# Fsociety_Keyboard_SCH_Cherry.net
KiCad netlist of a schematic drawn in Altium Designer
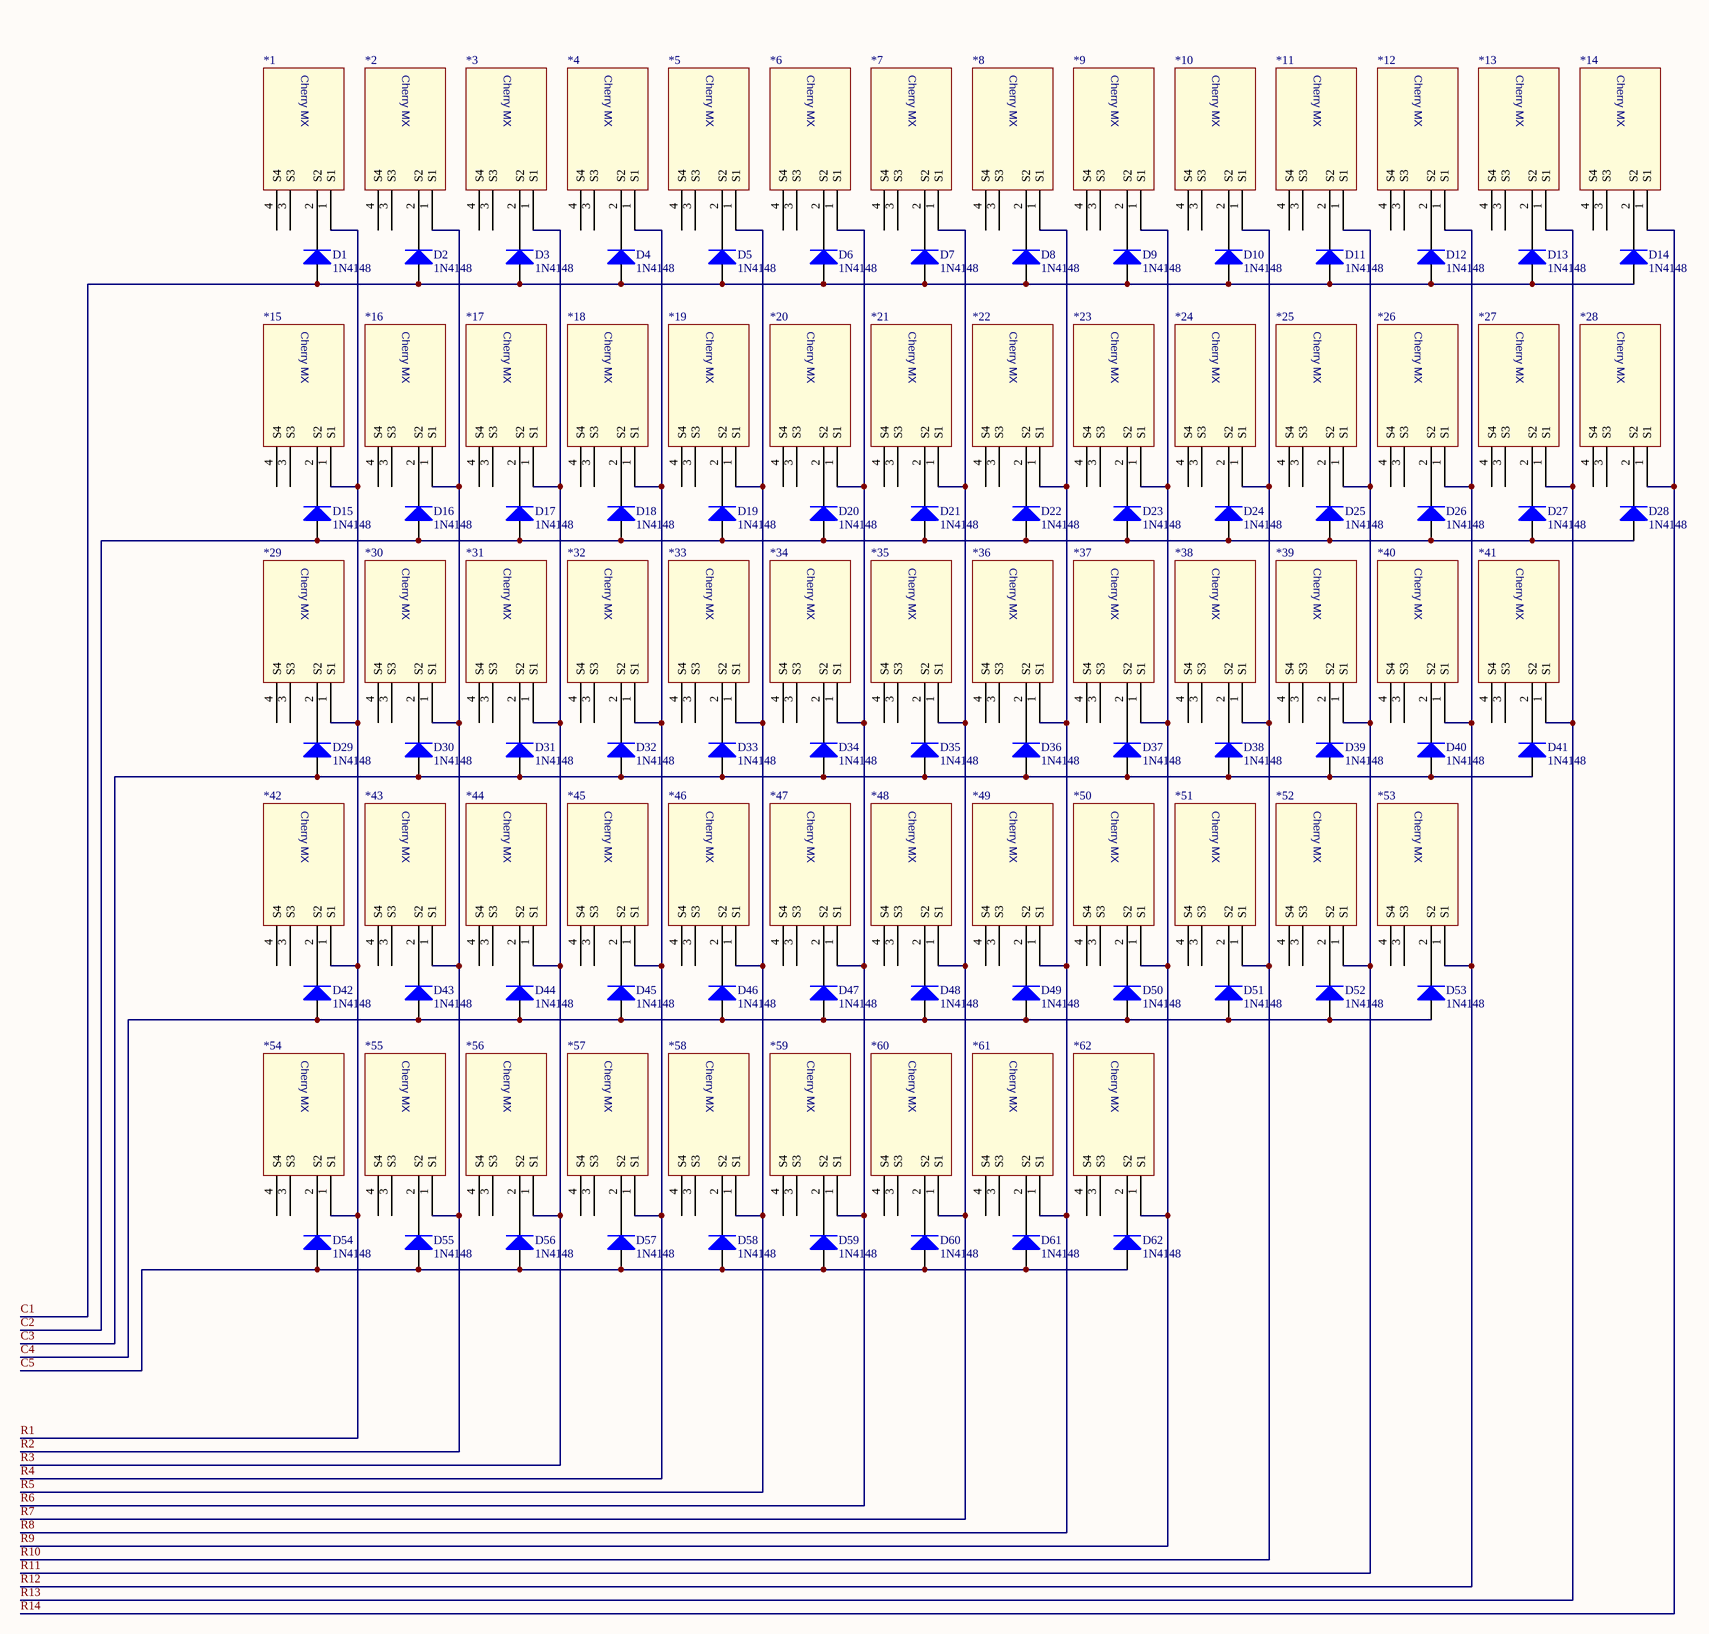
[diagram p0: Fsociety_Keyboard_SCH_Cherry.SchDoc]

(export (version "E")
  (design (tool "Eeschema 10.0.6"))
  (components
    (comp (ref "*1")
      (value "CHERRY_MX")
      (footprint "CherryMX")
      (libsource (lib "Sumasta_new") (part "CHERRY_MX"))
    )
    (comp (ref "*2")
      (value "CHERRY_MX")
      (footprint "CherryMX")
      (libsource (lib "Sumasta_new") (part "CHERRY_MX"))
    )
    (comp (ref "*3")
      (value "CHERRY_MX")
      (footprint "CherryMX")
      (libsource (lib "Sumasta_new") (part "CHERRY_MX"))
    )
    (comp (ref "*4")
      (value "CHERRY_MX")
      (footprint "CherryMX")
      (libsource (lib "Sumasta_new") (part "CHERRY_MX"))
    )
    (comp (ref "*5")
      (value "CHERRY_MX")
      (footprint "CherryMX")
      (libsource (lib "Sumasta_new") (part "CHERRY_MX"))
    )
    (comp (ref "*6")
      (value "CHERRY_MX")
      (footprint "CherryMX")
      (libsource (lib "Sumasta_new") (part "CHERRY_MX"))
    )
    (comp (ref "*7")
      (value "CHERRY_MX")
      (footprint "CherryMX")
      (libsource (lib "Sumasta_new") (part "CHERRY_MX"))
    )
    (comp (ref "*8")
      (value "CHERRY_MX")
      (footprint "CherryMX")
      (libsource (lib "Sumasta_new") (part "CHERRY_MX"))
    )
    (comp (ref "*9")
      (value "CHERRY_MX")
      (footprint "CherryMX")
      (libsource (lib "Sumasta_new") (part "CHERRY_MX"))
    )
    (comp (ref "*10")
      (value "CHERRY_MX")
      (footprint "CherryMX")
      (libsource (lib "Sumasta_new") (part "CHERRY_MX"))
    )
    (comp (ref "*11")
      (value "CHERRY_MX")
      (footprint "CherryMX")
      (libsource (lib "Sumasta_new") (part "CHERRY_MX"))
    )
    (comp (ref "*12")
      (value "CHERRY_MX")
      (footprint "CherryMX")
      (libsource (lib "Sumasta_new") (part "CHERRY_MX"))
    )
    (comp (ref "*13")
      (value "CHERRY_MX")
      (footprint "CherryMX")
      (libsource (lib "Sumasta_new") (part "CHERRY_MX"))
    )
    (comp (ref "*14")
      (value "CHERRY_MX")
      (footprint "CherryMX")
      (libsource (lib "Sumasta_new") (part "CHERRY_MX"))
    )
    (comp (ref "*15")
      (value "CHERRY_MX")
      (footprint "CherryMX")
      (libsource (lib "Sumasta_new") (part "CHERRY_MX"))
    )
    (comp (ref "*16")
      (value "CHERRY_MX")
      (footprint "CherryMX")
      (libsource (lib "Sumasta_new") (part "CHERRY_MX"))
    )
    (comp (ref "*17")
      (value "CHERRY_MX")
      (footprint "CherryMX")
      (libsource (lib "Sumasta_new") (part "CHERRY_MX"))
    )
    (comp (ref "*18")
      (value "CHERRY_MX")
      (footprint "CherryMX")
      (libsource (lib "Sumasta_new") (part "CHERRY_MX"))
    )
    (comp (ref "*19")
      (value "CHERRY_MX")
      (footprint "CherryMX")
      (libsource (lib "Sumasta_new") (part "CHERRY_MX"))
    )
    (comp (ref "*20")
      (value "CHERRY_MX")
      (footprint "CherryMX")
      (libsource (lib "Sumasta_new") (part "CHERRY_MX"))
    )
    (comp (ref "*21")
      (value "CHERRY_MX")
      (footprint "CherryMX")
      (libsource (lib "Sumasta_new") (part "CHERRY_MX"))
    )
    (comp (ref "*22")
      (value "CHERRY_MX")
      (footprint "CherryMX")
      (libsource (lib "Sumasta_new") (part "CHERRY_MX"))
    )
    (comp (ref "*23")
      (value "CHERRY_MX")
      (footprint "CherryMX")
      (libsource (lib "Sumasta_new") (part "CHERRY_MX"))
    )
    (comp (ref "*24")
      (value "CHERRY_MX")
      (footprint "CherryMX")
      (libsource (lib "Sumasta_new") (part "CHERRY_MX"))
    )
    (comp (ref "*25")
      (value "CHERRY_MX")
      (footprint "CherryMX")
      (libsource (lib "Sumasta_new") (part "CHERRY_MX"))
    )
    (comp (ref "*26")
      (value "CHERRY_MX")
      (footprint "CherryMX")
      (libsource (lib "Sumasta_new") (part "CHERRY_MX"))
    )
    (comp (ref "*27")
      (value "CHERRY_MX")
      (footprint "CherryMX")
      (libsource (lib "Sumasta_new") (part "CHERRY_MX"))
    )
    (comp (ref "*28")
      (value "CHERRY_MX")
      (footprint "CherryMX")
      (libsource (lib "Sumasta_new") (part "CHERRY_MX"))
    )
    (comp (ref "*29")
      (value "CHERRY_MX")
      (footprint "CherryMX")
      (libsource (lib "Sumasta_new") (part "CHERRY_MX"))
    )
    (comp (ref "*30")
      (value "CHERRY_MX")
      (footprint "CherryMX")
      (libsource (lib "Sumasta_new") (part "CHERRY_MX"))
    )
    (comp (ref "*31")
      (value "CHERRY_MX")
      (footprint "CherryMX")
      (libsource (lib "Sumasta_new") (part "CHERRY_MX"))
    )
    (comp (ref "*32")
      (value "CHERRY_MX")
      (footprint "CherryMX")
      (libsource (lib "Sumasta_new") (part "CHERRY_MX"))
    )
    (comp (ref "*33")
      (value "CHERRY_MX")
      (footprint "CherryMX")
      (libsource (lib "Sumasta_new") (part "CHERRY_MX"))
    )
    (comp (ref "*34")
      (value "CHERRY_MX")
      (footprint "CherryMX")
      (libsource (lib "Sumasta_new") (part "CHERRY_MX"))
    )
    (comp (ref "*35")
      (value "CHERRY_MX")
      (footprint "CherryMX")
      (libsource (lib "Sumasta_new") (part "CHERRY_MX"))
    )
    (comp (ref "*36")
      (value "CHERRY_MX")
      (footprint "CherryMX")
      (libsource (lib "Sumasta_new") (part "CHERRY_MX"))
    )
    (comp (ref "*37")
      (value "CHERRY_MX")
      (footprint "CherryMX")
      (libsource (lib "Sumasta_new") (part "CHERRY_MX"))
    )
    (comp (ref "*38")
      (value "CHERRY_MX")
      (footprint "CherryMX")
      (libsource (lib "Sumasta_new") (part "CHERRY_MX"))
    )
    (comp (ref "*39")
      (value "CHERRY_MX")
      (footprint "CherryMX")
      (libsource (lib "Sumasta_new") (part "CHERRY_MX"))
    )
    (comp (ref "*40")
      (value "CHERRY_MX")
      (footprint "CherryMX")
      (libsource (lib "Sumasta_new") (part "CHERRY_MX"))
    )
    (comp (ref "*41")
      (value "CHERRY_MX")
      (footprint "CherryMX")
      (libsource (lib "Sumasta_new") (part "CHERRY_MX"))
    )
    (comp (ref "*42")
      (value "CHERRY_MX")
      (footprint "CherryMX")
      (libsource (lib "Sumasta_new") (part "CHERRY_MX"))
    )
    (comp (ref "*43")
      (value "CHERRY_MX")
      (footprint "CherryMX")
      (libsource (lib "Sumasta_new") (part "CHERRY_MX"))
    )
    (comp (ref "*44")
      (value "CHERRY_MX")
      (footprint "CherryMX")
      (libsource (lib "Sumasta_new") (part "CHERRY_MX"))
    )
    (comp (ref "*45")
      (value "CHERRY_MX")
      (footprint "CherryMX")
      (libsource (lib "Sumasta_new") (part "CHERRY_MX"))
    )
    (comp (ref "*46")
      (value "CHERRY_MX")
      (footprint "CherryMX")
      (libsource (lib "Sumasta_new") (part "CHERRY_MX"))
    )
    (comp (ref "*47")
      (value "CHERRY_MX")
      (footprint "CherryMX")
      (libsource (lib "Sumasta_new") (part "CHERRY_MX"))
    )
    (comp (ref "*48")
      (value "CHERRY_MX")
      (footprint "CherryMX")
      (libsource (lib "Sumasta_new") (part "CHERRY_MX"))
    )
    (comp (ref "*49")
      (value "CHERRY_MX")
      (footprint "CherryMX")
      (libsource (lib "Sumasta_new") (part "CHERRY_MX"))
    )
    (comp (ref "*50")
      (value "CHERRY_MX")
      (footprint "CherryMX")
      (libsource (lib "Sumasta_new") (part "CHERRY_MX"))
    )
    (comp (ref "*51")
      (value "CHERRY_MX")
      (footprint "CherryMX")
      (libsource (lib "Sumasta_new") (part "CHERRY_MX"))
    )
    (comp (ref "*52")
      (value "CHERRY_MX")
      (footprint "CherryMX")
      (libsource (lib "Sumasta_new") (part "CHERRY_MX"))
    )
    (comp (ref "*53")
      (value "CHERRY_MX")
      (footprint "CherryMX")
      (libsource (lib "Sumasta_new") (part "CHERRY_MX"))
    )
    (comp (ref "*54")
      (value "CHERRY_MX")
      (footprint "CherryMX")
      (libsource (lib "Sumasta_new") (part "CHERRY_MX"))
    )
    (comp (ref "*55")
      (value "CHERRY_MX")
      (footprint "CherryMX")
      (libsource (lib "Sumasta_new") (part "CHERRY_MX"))
    )
    (comp (ref "*56")
      (value "CHERRY_MX")
      (footprint "CherryMX")
      (libsource (lib "Sumasta_new") (part "CHERRY_MX"))
    )
    (comp (ref "*57")
      (value "CHERRY_MX")
      (footprint "CherryMX")
      (libsource (lib "Sumasta_new") (part "CHERRY_MX"))
    )
    (comp (ref "*58")
      (value "CHERRY_MX")
      (footprint "CherryMX")
      (libsource (lib "Sumasta_new") (part "CHERRY_MX"))
    )
    (comp (ref "*59")
      (value "CHERRY_MX")
      (footprint "CherryMX")
      (libsource (lib "Sumasta_new") (part "CHERRY_MX"))
    )
    (comp (ref "*60")
      (value "CHERRY_MX")
      (footprint "CherryMX")
      (libsource (lib "Sumasta_new") (part "CHERRY_MX"))
    )
    (comp (ref "*61")
      (value "CHERRY_MX")
      (footprint "CherryMX")
      (libsource (lib "Sumasta_new") (part "CHERRY_MX"))
    )
    (comp (ref "*62")
      (value "CHERRY_MX")
      (footprint "CherryMX")
      (libsource (lib "Sumasta_new") (part "CHERRY_MX"))
    )
    (comp (ref "D1")
      (value "1N4148")
      (footprint "DIOMELF3515_NR_SOD80C")
      (description "Diode 1N4148 SOD80(SMT)")
      (fields (field (name "MAXPARTNUMBER") "1N4148!") (field (name "PARTNUMBER") "LL4148-GS18-LF"))
      (libsource (lib "RENA Vault") (part "DIODE"))
    )
    (comp (ref "D2")
      (value "1N4148")
      (footprint "DIOMELF3515_NR_SOD80C")
      (description "Diode 1N4148 SOD80(SMT)")
      (fields (field (name "MAXPARTNUMBER") "1N4148!") (field (name "PARTNUMBER") "LL4148-GS18-LF"))
      (libsource (lib "RENA Vault") (part "DIODE"))
    )
    (comp (ref "D3")
      (value "1N4148")
      (footprint "DIOMELF3515_NR_SOD80C")
      (description "Diode 1N4148 SOD80(SMT)")
      (fields (field (name "MAXPARTNUMBER") "1N4148!") (field (name "PARTNUMBER") "LL4148-GS18-LF"))
      (libsource (lib "RENA Vault") (part "DIODE"))
    )
    (comp (ref "D4")
      (value "1N4148")
      (footprint "DIOMELF3515_NR_SOD80C")
      (description "Diode 1N4148 SOD80(SMT)")
      (fields (field (name "MAXPARTNUMBER") "1N4148!") (field (name "PARTNUMBER") "LL4148-GS18-LF"))
      (libsource (lib "RENA Vault") (part "DIODE"))
    )
    (comp (ref "D5")
      (value "1N4148")
      (footprint "DIOMELF3515_NR_SOD80C")
      (description "Diode 1N4148 SOD80(SMT)")
      (fields (field (name "MAXPARTNUMBER") "1N4148!") (field (name "PARTNUMBER") "LL4148-GS18-LF"))
      (libsource (lib "RENA Vault") (part "DIODE"))
    )
    (comp (ref "D6")
      (value "1N4148")
      (footprint "DIOMELF3515_NR_SOD80C")
      (description "Diode 1N4148 SOD80(SMT)")
      (fields (field (name "MAXPARTNUMBER") "1N4148!") (field (name "PARTNUMBER") "LL4148-GS18-LF"))
      (libsource (lib "RENA Vault") (part "DIODE"))
    )
    (comp (ref "D7")
      (value "1N4148")
      (footprint "DIOMELF3515_NR_SOD80C")
      (description "Diode 1N4148 SOD80(SMT)")
      (fields (field (name "MAXPARTNUMBER") "1N4148!") (field (name "PARTNUMBER") "LL4148-GS18-LF"))
      (libsource (lib "RENA Vault") (part "DIODE"))
    )
    (comp (ref "D8")
      (value "1N4148")
      (footprint "DIOMELF3515_NR_SOD80C")
      (description "Diode 1N4148 SOD80(SMT)")
      (fields (field (name "MAXPARTNUMBER") "1N4148!") (field (name "PARTNUMBER") "LL4148-GS18-LF"))
      (libsource (lib "RENA Vault") (part "DIODE"))
    )
    (comp (ref "D9")
      (value "1N4148")
      (footprint "DIOMELF3515_NR_SOD80C")
      (description "Diode 1N4148 SOD80(SMT)")
      (fields (field (name "MAXPARTNUMBER") "1N4148!") (field (name "PARTNUMBER") "LL4148-GS18-LF"))
      (libsource (lib "RENA Vault") (part "DIODE"))
    )
    (comp (ref "D10")
      (value "1N4148")
      (footprint "DIOMELF3515_NR_SOD80C")
      (description "Diode 1N4148 SOD80(SMT)")
      (fields (field (name "MAXPARTNUMBER") "1N4148!") (field (name "PARTNUMBER") "LL4148-GS18-LF"))
      (libsource (lib "RENA Vault") (part "DIODE"))
    )
    (comp (ref "D11")
      (value "1N4148")
      (footprint "DIOMELF3515_NR_SOD80C")
      (description "Diode 1N4148 SOD80(SMT)")
      (fields (field (name "MAXPARTNUMBER") "1N4148!") (field (name "PARTNUMBER") "LL4148-GS18-LF"))
      (libsource (lib "RENA Vault") (part "DIODE"))
    )
    (comp (ref "D12")
      (value "1N4148")
      (footprint "DIOMELF3515_NR_SOD80C")
      (description "Diode 1N4148 SOD80(SMT)")
      (fields (field (name "MAXPARTNUMBER") "1N4148!") (field (name "PARTNUMBER") "LL4148-GS18-LF"))
      (libsource (lib "RENA Vault") (part "DIODE"))
    )
    (comp (ref "D13")
      (value "1N4148")
      (footprint "DIOMELF3515_NR_SOD80C")
      (description "Diode 1N4148 SOD80(SMT)")
      (fields (field (name "MAXPARTNUMBER") "1N4148!") (field (name "PARTNUMBER") "LL4148-GS18-LF"))
      (libsource (lib "RENA Vault") (part "DIODE"))
    )
    (comp (ref "D14")
      (value "1N4148")
      (footprint "DIOMELF3515_NR_SOD80C")
      (description "Diode 1N4148 SOD80(SMT)")
      (fields (field (name "MAXPARTNUMBER") "1N4148!") (field (name "PARTNUMBER") "LL4148-GS18-LF"))
      (libsource (lib "RENA Vault") (part "DIODE"))
    )
    (comp (ref "D15")
      (value "1N4148")
      (footprint "DIOMELF3515_NR_SOD80C")
      (description "Diode 1N4148 SOD80(SMT)")
      (fields (field (name "MAXPARTNUMBER") "1N4148!") (field (name "PARTNUMBER") "LL4148-GS18-LF"))
      (libsource (lib "RENA Vault") (part "DIODE"))
    )
    (comp (ref "D16")
      (value "1N4148")
      (footprint "DIOMELF3515_NR_SOD80C")
      (description "Diode 1N4148 SOD80(SMT)")
      (fields (field (name "MAXPARTNUMBER") "1N4148!") (field (name "PARTNUMBER") "LL4148-GS18-LF"))
      (libsource (lib "RENA Vault") (part "DIODE"))
    )
    (comp (ref "D17")
      (value "1N4148")
      (footprint "DIOMELF3515_NR_SOD80C")
      (description "Diode 1N4148 SOD80(SMT)")
      (fields (field (name "MAXPARTNUMBER") "1N4148!") (field (name "PARTNUMBER") "LL4148-GS18-LF"))
      (libsource (lib "RENA Vault") (part "DIODE"))
    )
    (comp (ref "D18")
      (value "1N4148")
      (footprint "DIOMELF3515_NR_SOD80C")
      (description "Diode 1N4148 SOD80(SMT)")
      (fields (field (name "MAXPARTNUMBER") "1N4148!") (field (name "PARTNUMBER") "LL4148-GS18-LF"))
      (libsource (lib "RENA Vault") (part "DIODE"))
    )
    (comp (ref "D19")
      (value "1N4148")
      (footprint "DIOMELF3515_NR_SOD80C")
      (description "Diode 1N4148 SOD80(SMT)")
      (fields (field (name "MAXPARTNUMBER") "1N4148!") (field (name "PARTNUMBER") "LL4148-GS18-LF"))
      (libsource (lib "RENA Vault") (part "DIODE"))
    )
    (comp (ref "D20")
      (value "1N4148")
      (footprint "DIOMELF3515_NR_SOD80C")
      (description "Diode 1N4148 SOD80(SMT)")
      (fields (field (name "MAXPARTNUMBER") "1N4148!") (field (name "PARTNUMBER") "LL4148-GS18-LF"))
      (libsource (lib "RENA Vault") (part "DIODE"))
    )
    (comp (ref "D21")
      (value "1N4148")
      (footprint "DIOMELF3515_NR_SOD80C")
      (description "Diode 1N4148 SOD80(SMT)")
      (fields (field (name "MAXPARTNUMBER") "1N4148!") (field (name "PARTNUMBER") "LL4148-GS18-LF"))
      (libsource (lib "RENA Vault") (part "DIODE"))
    )
    (comp (ref "D22")
      (value "1N4148")
      (footprint "DIOMELF3515_NR_SOD80C")
      (description "Diode 1N4148 SOD80(SMT)")
      (fields (field (name "MAXPARTNUMBER") "1N4148!") (field (name "PARTNUMBER") "LL4148-GS18-LF"))
      (libsource (lib "RENA Vault") (part "DIODE"))
    )
    (comp (ref "D23")
      (value "1N4148")
      (footprint "DIOMELF3515_NR_SOD80C")
      (description "Diode 1N4148 SOD80(SMT)")
      (fields (field (name "MAXPARTNUMBER") "1N4148!") (field (name "PARTNUMBER") "LL4148-GS18-LF"))
      (libsource (lib "RENA Vault") (part "DIODE"))
    )
    (comp (ref "D24")
      (value "1N4148")
      (footprint "DIOMELF3515_NR_SOD80C")
      (description "Diode 1N4148 SOD80(SMT)")
      (fields (field (name "MAXPARTNUMBER") "1N4148!") (field (name "PARTNUMBER") "LL4148-GS18-LF"))
      (libsource (lib "RENA Vault") (part "DIODE"))
    )
    (comp (ref "D25")
      (value "1N4148")
      (footprint "DIOMELF3515_NR_SOD80C")
      (description "Diode 1N4148 SOD80(SMT)")
      (fields (field (name "MAXPARTNUMBER") "1N4148!") (field (name "PARTNUMBER") "LL4148-GS18-LF"))
      (libsource (lib "RENA Vault") (part "DIODE"))
    )
    (comp (ref "D26")
      (value "1N4148")
      (footprint "DIOMELF3515_NR_SOD80C")
      (description "Diode 1N4148 SOD80(SMT)")
      (fields (field (name "MAXPARTNUMBER") "1N4148!") (field (name "PARTNUMBER") "LL4148-GS18-LF"))
      (libsource (lib "RENA Vault") (part "DIODE"))
    )
    (comp (ref "D27")
      (value "1N4148")
      (footprint "DIOMELF3515_NR_SOD80C")
      (description "Diode 1N4148 SOD80(SMT)")
      (fields (field (name "MAXPARTNUMBER") "1N4148!") (field (name "PARTNUMBER") "LL4148-GS18-LF"))
      (libsource (lib "RENA Vault") (part "DIODE"))
    )
    (comp (ref "D28")
      (value "1N4148")
      (footprint "DIOMELF3515_NR_SOD80C")
      (description "Diode 1N4148 SOD80(SMT)")
      (fields (field (name "MAXPARTNUMBER") "1N4148!") (field (name "PARTNUMBER") "LL4148-GS18-LF"))
      (libsource (lib "RENA Vault") (part "DIODE"))
    )
    (comp (ref "D29")
      (value "1N4148")
      (footprint "DIOMELF3515_NR_SOD80C")
      (description "Diode 1N4148 SOD80(SMT)")
      (fields (field (name "MAXPARTNUMBER") "1N4148!") (field (name "PARTNUMBER") "LL4148-GS18-LF"))
      (libsource (lib "RENA Vault") (part "DIODE"))
    )
    (comp (ref "D30")
      (value "1N4148")
      (footprint "DIOMELF3515_NR_SOD80C")
      (description "Diode 1N4148 SOD80(SMT)")
      (fields (field (name "MAXPARTNUMBER") "1N4148!") (field (name "PARTNUMBER") "LL4148-GS18-LF"))
      (libsource (lib "RENA Vault") (part "DIODE"))
    )
    (comp (ref "D31")
      (value "1N4148")
      (footprint "DIOMELF3515_NR_SOD80C")
      (description "Diode 1N4148 SOD80(SMT)")
      (fields (field (name "MAXPARTNUMBER") "1N4148!") (field (name "PARTNUMBER") "LL4148-GS18-LF"))
      (libsource (lib "RENA Vault") (part "DIODE"))
    )
    (comp (ref "D32")
      (value "1N4148")
      (footprint "DIOMELF3515_NR_SOD80C")
      (description "Diode 1N4148 SOD80(SMT)")
      (fields (field (name "MAXPARTNUMBER") "1N4148!") (field (name "PARTNUMBER") "LL4148-GS18-LF"))
      (libsource (lib "RENA Vault") (part "DIODE"))
    )
    (comp (ref "D33")
      (value "1N4148")
      (footprint "DIOMELF3515_NR_SOD80C")
      (description "Diode 1N4148 SOD80(SMT)")
      (fields (field (name "MAXPARTNUMBER") "1N4148!") (field (name "PARTNUMBER") "LL4148-GS18-LF"))
      (libsource (lib "RENA Vault") (part "DIODE"))
    )
    (comp (ref "D34")
      (value "1N4148")
      (footprint "DIOMELF3515_NR_SOD80C")
      (description "Diode 1N4148 SOD80(SMT)")
      (fields (field (name "MAXPARTNUMBER") "1N4148!") (field (name "PARTNUMBER") "LL4148-GS18-LF"))
      (libsource (lib "RENA Vault") (part "DIODE"))
    )
    (comp (ref "D35")
      (value "1N4148")
      (footprint "DIOMELF3515_NR_SOD80C")
      (description "Diode 1N4148 SOD80(SMT)")
      (fields (field (name "MAXPARTNUMBER") "1N4148!") (field (name "PARTNUMBER") "LL4148-GS18-LF"))
      (libsource (lib "RENA Vault") (part "DIODE"))
    )
    (comp (ref "D36")
      (value "1N4148")
      (footprint "DIOMELF3515_NR_SOD80C")
      (description "Diode 1N4148 SOD80(SMT)")
      (fields (field (name "MAXPARTNUMBER") "1N4148!") (field (name "PARTNUMBER") "LL4148-GS18-LF"))
      (libsource (lib "RENA Vault") (part "DIODE"))
    )
    (comp (ref "D37")
      (value "1N4148")
      (footprint "DIOMELF3515_NR_SOD80C")
      (description "Diode 1N4148 SOD80(SMT)")
      (fields (field (name "MAXPARTNUMBER") "1N4148!") (field (name "PARTNUMBER") "LL4148-GS18-LF"))
      (libsource (lib "RENA Vault") (part "DIODE"))
    )
    (comp (ref "D38")
      (value "1N4148")
      (footprint "DIOMELF3515_NR_SOD80C")
      (description "Diode 1N4148 SOD80(SMT)")
      (fields (field (name "MAXPARTNUMBER") "1N4148!") (field (name "PARTNUMBER") "LL4148-GS18-LF"))
      (libsource (lib "RENA Vault") (part "DIODE"))
    )
    (comp (ref "D39")
      (value "1N4148")
      (footprint "DIOMELF3515_NR_SOD80C")
      (description "Diode 1N4148 SOD80(SMT)")
      (fields (field (name "MAXPARTNUMBER") "1N4148!") (field (name "PARTNUMBER") "LL4148-GS18-LF"))
      (libsource (lib "RENA Vault") (part "DIODE"))
    )
    (comp (ref "D40")
      (value "1N4148")
      (footprint "DIOMELF3515_NR_SOD80C")
      (description "Diode 1N4148 SOD80(SMT)")
      (fields (field (name "MAXPARTNUMBER") "1N4148!") (field (name "PARTNUMBER") "LL4148-GS18-LF"))
      (libsource (lib "RENA Vault") (part "DIODE"))
    )
    (comp (ref "D41")
      (value "1N4148")
      (footprint "DIOMELF3515_NR_SOD80C")
      (description "Diode 1N4148 SOD80(SMT)")
      (fields (field (name "MAXPARTNUMBER") "1N4148!") (field (name "PARTNUMBER") "LL4148-GS18-LF"))
      (libsource (lib "RENA Vault") (part "DIODE"))
    )
    (comp (ref "D42")
      (value "1N4148")
      (footprint "DIOMELF3515_NR_SOD80C")
      (description "Diode 1N4148 SOD80(SMT)")
      (fields (field (name "MAXPARTNUMBER") "1N4148!") (field (name "PARTNUMBER") "LL4148-GS18-LF"))
      (libsource (lib "RENA Vault") (part "DIODE"))
    )
    (comp (ref "D43")
      (value "1N4148")
      (footprint "DIOMELF3515_NR_SOD80C")
      (description "Diode 1N4148 SOD80(SMT)")
      (fields (field (name "MAXPARTNUMBER") "1N4148!") (field (name "PARTNUMBER") "LL4148-GS18-LF"))
      (libsource (lib "RENA Vault") (part "DIODE"))
    )
    (comp (ref "D44")
      (value "1N4148")
      (footprint "DIOMELF3515_NR_SOD80C")
      (description "Diode 1N4148 SOD80(SMT)")
      (fields (field (name "MAXPARTNUMBER") "1N4148!") (field (name "PARTNUMBER") "LL4148-GS18-LF"))
      (libsource (lib "RENA Vault") (part "DIODE"))
    )
    (comp (ref "D45")
      (value "1N4148")
      (footprint "DIOMELF3515_NR_SOD80C")
      (description "Diode 1N4148 SOD80(SMT)")
      (fields (field (name "MAXPARTNUMBER") "1N4148!") (field (name "PARTNUMBER") "LL4148-GS18-LF"))
      (libsource (lib "RENA Vault") (part "DIODE"))
    )
    (comp (ref "D46")
      (value "1N4148")
      (footprint "DIOMELF3515_NR_SOD80C")
      (description "Diode 1N4148 SOD80(SMT)")
      (fields (field (name "MAXPARTNUMBER") "1N4148!") (field (name "PARTNUMBER") "LL4148-GS18-LF"))
      (libsource (lib "RENA Vault") (part "DIODE"))
    )
    (comp (ref "D47")
      (value "1N4148")
      (footprint "DIOMELF3515_NR_SOD80C")
      (description "Diode 1N4148 SOD80(SMT)")
      (fields (field (name "MAXPARTNUMBER") "1N4148!") (field (name "PARTNUMBER") "LL4148-GS18-LF"))
      (libsource (lib "RENA Vault") (part "DIODE"))
    )
    (comp (ref "D48")
      (value "1N4148")
      (footprint "DIOMELF3515_NR_SOD80C")
      (description "Diode 1N4148 SOD80(SMT)")
      (fields (field (name "MAXPARTNUMBER") "1N4148!") (field (name "PARTNUMBER") "LL4148-GS18-LF"))
      (libsource (lib "RENA Vault") (part "DIODE"))
    )
    (comp (ref "D49")
      (value "1N4148")
      (footprint "DIOMELF3515_NR_SOD80C")
      (description "Diode 1N4148 SOD80(SMT)")
      (fields (field (name "MAXPARTNUMBER") "1N4148!") (field (name "PARTNUMBER") "LL4148-GS18-LF"))
      (libsource (lib "RENA Vault") (part "DIODE"))
    )
    (comp (ref "D50")
      (value "1N4148")
      (footprint "DIOMELF3515_NR_SOD80C")
      (description "Diode 1N4148 SOD80(SMT)")
      (fields (field (name "MAXPARTNUMBER") "1N4148!") (field (name "PARTNUMBER") "LL4148-GS18-LF"))
      (libsource (lib "RENA Vault") (part "DIODE"))
    )
    (comp (ref "D51")
      (value "1N4148")
      (footprint "DIOMELF3515_NR_SOD80C")
      (description "Diode 1N4148 SOD80(SMT)")
      (fields (field (name "MAXPARTNUMBER") "1N4148!") (field (name "PARTNUMBER") "LL4148-GS18-LF"))
      (libsource (lib "RENA Vault") (part "DIODE"))
    )
    (comp (ref "D52")
      (value "1N4148")
      (footprint "DIOMELF3515_NR_SOD80C")
      (description "Diode 1N4148 SOD80(SMT)")
      (fields (field (name "MAXPARTNUMBER") "1N4148!") (field (name "PARTNUMBER") "LL4148-GS18-LF"))
      (libsource (lib "RENA Vault") (part "DIODE"))
    )
    (comp (ref "D53")
      (value "1N4148")
      (footprint "DIOMELF3515_NR_SOD80C")
      (description "Diode 1N4148 SOD80(SMT)")
      (fields (field (name "MAXPARTNUMBER") "1N4148!") (field (name "PARTNUMBER") "LL4148-GS18-LF"))
      (libsource (lib "RENA Vault") (part "DIODE"))
    )
    (comp (ref "D54")
      (value "1N4148")
      (footprint "DIOMELF3515_NR_SOD80C")
      (description "Diode 1N4148 SOD80(SMT)")
      (fields (field (name "MAXPARTNUMBER") "1N4148!") (field (name "PARTNUMBER") "LL4148-GS18-LF"))
      (libsource (lib "RENA Vault") (part "DIODE"))
    )
    (comp (ref "D55")
      (value "1N4148")
      (footprint "DIOMELF3515_NR_SOD80C")
      (description "Diode 1N4148 SOD80(SMT)")
      (fields (field (name "MAXPARTNUMBER") "1N4148!") (field (name "PARTNUMBER") "LL4148-GS18-LF"))
      (libsource (lib "RENA Vault") (part "DIODE"))
    )
    (comp (ref "D56")
      (value "1N4148")
      (footprint "DIOMELF3515_NR_SOD80C")
      (description "Diode 1N4148 SOD80(SMT)")
      (fields (field (name "MAXPARTNUMBER") "1N4148!") (field (name "PARTNUMBER") "LL4148-GS18-LF"))
      (libsource (lib "RENA Vault") (part "DIODE"))
    )
    (comp (ref "D57")
      (value "1N4148")
      (footprint "DIOMELF3515_NR_SOD80C")
      (description "Diode 1N4148 SOD80(SMT)")
      (fields (field (name "MAXPARTNUMBER") "1N4148!") (field (name "PARTNUMBER") "LL4148-GS18-LF"))
      (libsource (lib "RENA Vault") (part "DIODE"))
    )
    (comp (ref "D58")
      (value "1N4148")
      (footprint "DIOMELF3515_NR_SOD80C")
      (description "Diode 1N4148 SOD80(SMT)")
      (fields (field (name "MAXPARTNUMBER") "1N4148!") (field (name "PARTNUMBER") "LL4148-GS18-LF"))
      (libsource (lib "RENA Vault") (part "DIODE"))
    )
    (comp (ref "D59")
      (value "1N4148")
      (footprint "DIOMELF3515_NR_SOD80C")
      (description "Diode 1N4148 SOD80(SMT)")
      (fields (field (name "MAXPARTNUMBER") "1N4148!") (field (name "PARTNUMBER") "LL4148-GS18-LF"))
      (libsource (lib "RENA Vault") (part "DIODE"))
    )
    (comp (ref "D60")
      (value "1N4148")
      (footprint "DIOMELF3515_NR_SOD80C")
      (description "Diode 1N4148 SOD80(SMT)")
      (fields (field (name "MAXPARTNUMBER") "1N4148!") (field (name "PARTNUMBER") "LL4148-GS18-LF"))
      (libsource (lib "RENA Vault") (part "DIODE"))
    )
    (comp (ref "D61")
      (value "1N4148")
      (footprint "DIOMELF3515_NR_SOD80C")
      (description "Diode 1N4148 SOD80(SMT)")
      (fields (field (name "MAXPARTNUMBER") "1N4148!") (field (name "PARTNUMBER") "LL4148-GS18-LF"))
      (libsource (lib "RENA Vault") (part "DIODE"))
    )
    (comp (ref "D62")
      (value "1N4148")
      (footprint "DIOMELF3515_NR_SOD80C")
      (description "Diode 1N4148 SOD80(SMT)")
      (fields (field (name "MAXPARTNUMBER") "1N4148!") (field (name "PARTNUMBER") "LL4148-GS18-LF"))
      (libsource (lib "RENA Vault") (part "DIODE"))
    )
  )
  (nets
    (net (code "1") (name "/C1") (class "Default")
      (node (ref "D1") (pin "A") (pinfunction "A_A") (pintype "passive"))
      (node (ref "D10") (pin "A") (pinfunction "A_A") (pintype "passive"))
      (node (ref "D11") (pin "A") (pinfunction "A_A") (pintype "passive"))
      (node (ref "D12") (pin "A") (pinfunction "A_A") (pintype "passive"))
      (node (ref "D13") (pin "A") (pinfunction "A_A") (pintype "passive"))
      (node (ref "D14") (pin "A") (pinfunction "A_A") (pintype "passive"))
      (node (ref "D2") (pin "A") (pinfunction "A_A") (pintype "passive"))
      (node (ref "D3") (pin "A") (pinfunction "A_A") (pintype "passive"))
      (node (ref "D4") (pin "A") (pinfunction "A_A") (pintype "passive"))
      (node (ref "D5") (pin "A") (pinfunction "A_A") (pintype "passive"))
      (node (ref "D6") (pin "A") (pinfunction "A_A") (pintype "passive"))
      (node (ref "D7") (pin "A") (pinfunction "A_A") (pintype "passive"))
      (node (ref "D8") (pin "A") (pinfunction "A_A") (pintype "passive"))
      (node (ref "D9") (pin "A") (pinfunction "A_A") (pintype "passive"))
    )
    (net (code "2") (name "/C2") (class "Default")
      (node (ref "D15") (pin "A") (pinfunction "A_A") (pintype "passive"))
      (node (ref "D16") (pin "A") (pinfunction "A_A") (pintype "passive"))
      (node (ref "D17") (pin "A") (pinfunction "A_A") (pintype "passive"))
      (node (ref "D18") (pin "A") (pinfunction "A_A") (pintype "passive"))
      (node (ref "D19") (pin "A") (pinfunction "A_A") (pintype "passive"))
      (node (ref "D20") (pin "A") (pinfunction "A_A") (pintype "passive"))
      (node (ref "D21") (pin "A") (pinfunction "A_A") (pintype "passive"))
      (node (ref "D22") (pin "A") (pinfunction "A_A") (pintype "passive"))
      (node (ref "D23") (pin "A") (pinfunction "A_A") (pintype "passive"))
      (node (ref "D24") (pin "A") (pinfunction "A_A") (pintype "passive"))
      (node (ref "D25") (pin "A") (pinfunction "A_A") (pintype "passive"))
      (node (ref "D26") (pin "A") (pinfunction "A_A") (pintype "passive"))
      (node (ref "D27") (pin "A") (pinfunction "A_A") (pintype "passive"))
      (node (ref "D28") (pin "A") (pinfunction "A_A") (pintype "passive"))
    )
    (net (code "3") (name "/C3") (class "Default")
      (node (ref "D29") (pin "A") (pinfunction "A_A") (pintype "passive"))
      (node (ref "D30") (pin "A") (pinfunction "A_A") (pintype "passive"))
      (node (ref "D31") (pin "A") (pinfunction "A_A") (pintype "passive"))
      (node (ref "D32") (pin "A") (pinfunction "A_A") (pintype "passive"))
      (node (ref "D33") (pin "A") (pinfunction "A_A") (pintype "passive"))
      (node (ref "D34") (pin "A") (pinfunction "A_A") (pintype "passive"))
      (node (ref "D35") (pin "A") (pinfunction "A_A") (pintype "passive"))
      (node (ref "D36") (pin "A") (pinfunction "A_A") (pintype "passive"))
      (node (ref "D37") (pin "A") (pinfunction "A_A") (pintype "passive"))
      (node (ref "D38") (pin "A") (pinfunction "A_A") (pintype "passive"))
      (node (ref "D39") (pin "A") (pinfunction "A_A") (pintype "passive"))
      (node (ref "D40") (pin "A") (pinfunction "A_A") (pintype "passive"))
      (node (ref "D41") (pin "A") (pinfunction "A_A") (pintype "passive"))
    )
    (net (code "4") (name "/C4") (class "Default")
      (node (ref "D42") (pin "A") (pinfunction "A_A") (pintype "passive"))
      (node (ref "D43") (pin "A") (pinfunction "A_A") (pintype "passive"))
      (node (ref "D44") (pin "A") (pinfunction "A_A") (pintype "passive"))
      (node (ref "D45") (pin "A") (pinfunction "A_A") (pintype "passive"))
      (node (ref "D46") (pin "A") (pinfunction "A_A") (pintype "passive"))
      (node (ref "D47") (pin "A") (pinfunction "A_A") (pintype "passive"))
      (node (ref "D48") (pin "A") (pinfunction "A_A") (pintype "passive"))
      (node (ref "D49") (pin "A") (pinfunction "A_A") (pintype "passive"))
      (node (ref "D50") (pin "A") (pinfunction "A_A") (pintype "passive"))
      (node (ref "D51") (pin "A") (pinfunction "A_A") (pintype "passive"))
      (node (ref "D52") (pin "A") (pinfunction "A_A") (pintype "passive"))
      (node (ref "D53") (pin "A") (pinfunction "A_A") (pintype "passive"))
    )
    (net (code "5") (name "/C5") (class "Default")
      (node (ref "D54") (pin "A") (pinfunction "A_A") (pintype "passive"))
      (node (ref "D55") (pin "A") (pinfunction "A_A") (pintype "passive"))
      (node (ref "D56") (pin "A") (pinfunction "A_A") (pintype "passive"))
      (node (ref "D57") (pin "A") (pinfunction "A_A") (pintype "passive"))
      (node (ref "D58") (pin "A") (pinfunction "A_A") (pintype "passive"))
      (node (ref "D59") (pin "A") (pinfunction "A_A") (pintype "passive"))
      (node (ref "D60") (pin "A") (pinfunction "A_A") (pintype "passive"))
      (node (ref "D61") (pin "A") (pinfunction "A_A") (pintype "passive"))
      (node (ref "D62") (pin "A") (pinfunction "A_A") (pintype "passive"))
    )
    (net (code "6") (name "/R1") (class "Default")
      (node (ref "*1") (pin "1") (pinfunction "S1_1") (pintype "passive"))
      (node (ref "*15") (pin "1") (pinfunction "S1_1") (pintype "passive"))
      (node (ref "*29") (pin "1") (pinfunction "S1_1") (pintype "passive"))
      (node (ref "*42") (pin "1") (pinfunction "S1_1") (pintype "passive"))
      (node (ref "*54") (pin "1") (pinfunction "S1_1") (pintype "passive"))
    )
    (net (code "7") (name "/R2") (class "Default")
      (node (ref "*16") (pin "1") (pinfunction "S1_1") (pintype "passive"))
      (node (ref "*2") (pin "1") (pinfunction "S1_1") (pintype "passive"))
      (node (ref "*30") (pin "1") (pinfunction "S1_1") (pintype "passive"))
      (node (ref "*43") (pin "1") (pinfunction "S1_1") (pintype "passive"))
      (node (ref "*55") (pin "1") (pinfunction "S1_1") (pintype "passive"))
    )
    (net (code "8") (name "/R3") (class "Default")
      (node (ref "*17") (pin "1") (pinfunction "S1_1") (pintype "passive"))
      (node (ref "*3") (pin "1") (pinfunction "S1_1") (pintype "passive"))
      (node (ref "*31") (pin "1") (pinfunction "S1_1") (pintype "passive"))
      (node (ref "*44") (pin "1") (pinfunction "S1_1") (pintype "passive"))
      (node (ref "*56") (pin "1") (pinfunction "S1_1") (pintype "passive"))
    )
    (net (code "9") (name "/R4") (class "Default")
      (node (ref "*18") (pin "1") (pinfunction "S1_1") (pintype "passive"))
      (node (ref "*32") (pin "1") (pinfunction "S1_1") (pintype "passive"))
      (node (ref "*4") (pin "1") (pinfunction "S1_1") (pintype "passive"))
      (node (ref "*45") (pin "1") (pinfunction "S1_1") (pintype "passive"))
      (node (ref "*57") (pin "1") (pinfunction "S1_1") (pintype "passive"))
    )
    (net (code "10") (name "/R5") (class "Default")
      (node (ref "*19") (pin "1") (pinfunction "S1_1") (pintype "passive"))
      (node (ref "*33") (pin "1") (pinfunction "S1_1") (pintype "passive"))
      (node (ref "*46") (pin "1") (pinfunction "S1_1") (pintype "passive"))
      (node (ref "*5") (pin "1") (pinfunction "S1_1") (pintype "passive"))
      (node (ref "*58") (pin "1") (pinfunction "S1_1") (pintype "passive"))
    )
    (net (code "11") (name "/R6") (class "Default")
      (node (ref "*20") (pin "1") (pinfunction "S1_1") (pintype "passive"))
      (node (ref "*34") (pin "1") (pinfunction "S1_1") (pintype "passive"))
      (node (ref "*47") (pin "1") (pinfunction "S1_1") (pintype "passive"))
      (node (ref "*59") (pin "1") (pinfunction "S1_1") (pintype "passive"))
      (node (ref "*6") (pin "1") (pinfunction "S1_1") (pintype "passive"))
    )
    (net (code "12") (name "/R7") (class "Default")
      (node (ref "*21") (pin "1") (pinfunction "S1_1") (pintype "passive"))
      (node (ref "*35") (pin "1") (pinfunction "S1_1") (pintype "passive"))
      (node (ref "*48") (pin "1") (pinfunction "S1_1") (pintype "passive"))
      (node (ref "*60") (pin "1") (pinfunction "S1_1") (pintype "passive"))
      (node (ref "*7") (pin "1") (pinfunction "S1_1") (pintype "passive"))
    )
    (net (code "13") (name "/R8") (class "Default")
      (node (ref "*22") (pin "1") (pinfunction "S1_1") (pintype "passive"))
      (node (ref "*36") (pin "1") (pinfunction "S1_1") (pintype "passive"))
      (node (ref "*49") (pin "1") (pinfunction "S1_1") (pintype "passive"))
      (node (ref "*61") (pin "1") (pinfunction "S1_1") (pintype "passive"))
      (node (ref "*8") (pin "1") (pinfunction "S1_1") (pintype "passive"))
    )
    (net (code "14") (name "/R9") (class "Default")
      (node (ref "*23") (pin "1") (pinfunction "S1_1") (pintype "passive"))
      (node (ref "*37") (pin "1") (pinfunction "S1_1") (pintype "passive"))
      (node (ref "*50") (pin "1") (pinfunction "S1_1") (pintype "passive"))
      (node (ref "*62") (pin "1") (pinfunction "S1_1") (pintype "passive"))
      (node (ref "*9") (pin "1") (pinfunction "S1_1") (pintype "passive"))
    )
    (net (code "15") (name "/R10") (class "Default")
      (node (ref "*10") (pin "1") (pinfunction "S1_1") (pintype "passive"))
      (node (ref "*24") (pin "1") (pinfunction "S1_1") (pintype "passive"))
      (node (ref "*38") (pin "1") (pinfunction "S1_1") (pintype "passive"))
      (node (ref "*51") (pin "1") (pinfunction "S1_1") (pintype "passive"))
    )
    (net (code "16") (name "/R11") (class "Default")
      (node (ref "*11") (pin "1") (pinfunction "S1_1") (pintype "passive"))
      (node (ref "*25") (pin "1") (pinfunction "S1_1") (pintype "passive"))
      (node (ref "*39") (pin "1") (pinfunction "S1_1") (pintype "passive"))
      (node (ref "*52") (pin "1") (pinfunction "S1_1") (pintype "passive"))
    )
    (net (code "17") (name "/R12") (class "Default")
      (node (ref "*12") (pin "1") (pinfunction "S1_1") (pintype "passive"))
      (node (ref "*26") (pin "1") (pinfunction "S1_1") (pintype "passive"))
      (node (ref "*40") (pin "1") (pinfunction "S1_1") (pintype "passive"))
      (node (ref "*53") (pin "1") (pinfunction "S1_1") (pintype "passive"))
    )
    (net (code "18") (name "/R13") (class "Default")
      (node (ref "*13") (pin "1") (pinfunction "S1_1") (pintype "passive"))
      (node (ref "*27") (pin "1") (pinfunction "S1_1") (pintype "passive"))
      (node (ref "*41") (pin "1") (pinfunction "S1_1") (pintype "passive"))
    )
    (net (code "19") (name "/R14") (class "Default")
      (node (ref "*14") (pin "1") (pinfunction "S1_1") (pintype "passive"))
      (node (ref "*28") (pin "1") (pinfunction "S1_1") (pintype "passive"))
    )
    (net (code "20") (name "Net-(*1-S2)") (class "Default")
      (node (ref "*1") (pin "2") (pinfunction "S2_2") (pintype "passive"))
      (node (ref "D1") (pin "C") (pinfunction "C_C") (pintype "passive"))
    )
    (net (code "21") (name "Net-(*2-S2)") (class "Default")
      (node (ref "*2") (pin "2") (pinfunction "S2_2") (pintype "passive"))
      (node (ref "D2") (pin "C") (pinfunction "C_C") (pintype "passive"))
    )
    (net (code "22") (name "Net-(*3-S2)") (class "Default")
      (node (ref "*3") (pin "2") (pinfunction "S2_2") (pintype "passive"))
      (node (ref "D3") (pin "C") (pinfunction "C_C") (pintype "passive"))
    )
    (net (code "23") (name "Net-(*4-S2)") (class "Default")
      (node (ref "*4") (pin "2") (pinfunction "S2_2") (pintype "passive"))
      (node (ref "D4") (pin "C") (pinfunction "C_C") (pintype "passive"))
    )
    (net (code "24") (name "Net-(*5-S2)") (class "Default")
      (node (ref "*5") (pin "2") (pinfunction "S2_2") (pintype "passive"))
      (node (ref "D5") (pin "C") (pinfunction "C_C") (pintype "passive"))
    )
    (net (code "25") (name "Net-(*6-S2)") (class "Default")
      (node (ref "*6") (pin "2") (pinfunction "S2_2") (pintype "passive"))
      (node (ref "D6") (pin "C") (pinfunction "C_C") (pintype "passive"))
    )
    (net (code "26") (name "Net-(*7-S2)") (class "Default")
      (node (ref "*7") (pin "2") (pinfunction "S2_2") (pintype "passive"))
      (node (ref "D7") (pin "C") (pinfunction "C_C") (pintype "passive"))
    )
    (net (code "27") (name "Net-(*8-S2)") (class "Default")
      (node (ref "*8") (pin "2") (pinfunction "S2_2") (pintype "passive"))
      (node (ref "D8") (pin "C") (pinfunction "C_C") (pintype "passive"))
    )
    (net (code "28") (name "Net-(*9-S2)") (class "Default")
      (node (ref "*9") (pin "2") (pinfunction "S2_2") (pintype "passive"))
      (node (ref "D9") (pin "C") (pinfunction "C_C") (pintype "passive"))
    )
    (net (code "29") (name "Net-(*10-S2)") (class "Default")
      (node (ref "*10") (pin "2") (pinfunction "S2_2") (pintype "passive"))
      (node (ref "D10") (pin "C") (pinfunction "C_C") (pintype "passive"))
    )
    (net (code "30") (name "Net-(*11-S2)") (class "Default")
      (node (ref "*11") (pin "2") (pinfunction "S2_2") (pintype "passive"))
      (node (ref "D11") (pin "C") (pinfunction "C_C") (pintype "passive"))
    )
    (net (code "31") (name "Net-(*12-S2)") (class "Default")
      (node (ref "*12") (pin "2") (pinfunction "S2_2") (pintype "passive"))
      (node (ref "D12") (pin "C") (pinfunction "C_C") (pintype "passive"))
    )
    (net (code "32") (name "Net-(*13-S2)") (class "Default")
      (node (ref "*13") (pin "2") (pinfunction "S2_2") (pintype "passive"))
      (node (ref "D13") (pin "C") (pinfunction "C_C") (pintype "passive"))
    )
    (net (code "33") (name "Net-(*14-S2)") (class "Default")
      (node (ref "*14") (pin "2") (pinfunction "S2_2") (pintype "passive"))
      (node (ref "D14") (pin "C") (pinfunction "C_C") (pintype "passive"))
    )
    (net (code "34") (name "Net-(*15-S2)") (class "Default")
      (node (ref "*15") (pin "2") (pinfunction "S2_2") (pintype "passive"))
      (node (ref "D15") (pin "C") (pinfunction "C_C") (pintype "passive"))
    )
    (net (code "35") (name "Net-(*16-S2)") (class "Default")
      (node (ref "*16") (pin "2") (pinfunction "S2_2") (pintype "passive"))
      (node (ref "D16") (pin "C") (pinfunction "C_C") (pintype "passive"))
    )
    (net (code "36") (name "Net-(*17-S2)") (class "Default")
      (node (ref "*17") (pin "2") (pinfunction "S2_2") (pintype "passive"))
      (node (ref "D17") (pin "C") (pinfunction "C_C") (pintype "passive"))
    )
    (net (code "37") (name "Net-(*18-S2)") (class "Default")
      (node (ref "*18") (pin "2") (pinfunction "S2_2") (pintype "passive"))
      (node (ref "D18") (pin "C") (pinfunction "C_C") (pintype "passive"))
    )
    (net (code "38") (name "Net-(*19-S2)") (class "Default")
      (node (ref "*19") (pin "2") (pinfunction "S2_2") (pintype "passive"))
      (node (ref "D19") (pin "C") (pinfunction "C_C") (pintype "passive"))
    )
    (net (code "39") (name "Net-(*20-S2)") (class "Default")
      (node (ref "*20") (pin "2") (pinfunction "S2_2") (pintype "passive"))
      (node (ref "D20") (pin "C") (pinfunction "C_C") (pintype "passive"))
    )
    (net (code "40") (name "Net-(*21-S2)") (class "Default")
      (node (ref "*21") (pin "2") (pinfunction "S2_2") (pintype "passive"))
      (node (ref "D21") (pin "C") (pinfunction "C_C") (pintype "passive"))
    )
    (net (code "41") (name "Net-(*22-S2)") (class "Default")
      (node (ref "*22") (pin "2") (pinfunction "S2_2") (pintype "passive"))
      (node (ref "D22") (pin "C") (pinfunction "C_C") (pintype "passive"))
    )
    (net (code "42") (name "Net-(*23-S2)") (class "Default")
      (node (ref "*23") (pin "2") (pinfunction "S2_2") (pintype "passive"))
      (node (ref "D23") (pin "C") (pinfunction "C_C") (pintype "passive"))
    )
    (net (code "43") (name "Net-(*24-S2)") (class "Default")
      (node (ref "*24") (pin "2") (pinfunction "S2_2") (pintype "passive"))
      (node (ref "D24") (pin "C") (pinfunction "C_C") (pintype "passive"))
    )
    (net (code "44") (name "Net-(*25-S2)") (class "Default")
      (node (ref "*25") (pin "2") (pinfunction "S2_2") (pintype "passive"))
      (node (ref "D25") (pin "C") (pinfunction "C_C") (pintype "passive"))
    )
    (net (code "45") (name "Net-(*26-S2)") (class "Default")
      (node (ref "*26") (pin "2") (pinfunction "S2_2") (pintype "passive"))
      (node (ref "D26") (pin "C") (pinfunction "C_C") (pintype "passive"))
    )
    (net (code "46") (name "Net-(*27-S2)") (class "Default")
      (node (ref "*27") (pin "2") (pinfunction "S2_2") (pintype "passive"))
      (node (ref "D27") (pin "C") (pinfunction "C_C") (pintype "passive"))
    )
    (net (code "47") (name "Net-(*28-S2)") (class "Default")
      (node (ref "*28") (pin "2") (pinfunction "S2_2") (pintype "passive"))
      (node (ref "D28") (pin "C") (pinfunction "C_C") (pintype "passive"))
    )
    (net (code "48") (name "Net-(*29-S2)") (class "Default")
      (node (ref "*29") (pin "2") (pinfunction "S2_2") (pintype "passive"))
      (node (ref "D29") (pin "C") (pinfunction "C_C") (pintype "passive"))
    )
    (net (code "49") (name "Net-(*30-S2)") (class "Default")
      (node (ref "*30") (pin "2") (pinfunction "S2_2") (pintype "passive"))
      (node (ref "D30") (pin "C") (pinfunction "C_C") (pintype "passive"))
    )
    (net (code "50") (name "Net-(*31-S2)") (class "Default")
      (node (ref "*31") (pin "2") (pinfunction "S2_2") (pintype "passive"))
      (node (ref "D31") (pin "C") (pinfunction "C_C") (pintype "passive"))
    )
    (net (code "51") (name "Net-(*32-S2)") (class "Default")
      (node (ref "*32") (pin "2") (pinfunction "S2_2") (pintype "passive"))
      (node (ref "D32") (pin "C") (pinfunction "C_C") (pintype "passive"))
    )
    (net (code "52") (name "Net-(*33-S2)") (class "Default")
      (node (ref "*33") (pin "2") (pinfunction "S2_2") (pintype "passive"))
      (node (ref "D33") (pin "C") (pinfunction "C_C") (pintype "passive"))
    )
    (net (code "53") (name "Net-(*34-S2)") (class "Default")
      (node (ref "*34") (pin "2") (pinfunction "S2_2") (pintype "passive"))
      (node (ref "D34") (pin "C") (pinfunction "C_C") (pintype "passive"))
    )
    (net (code "54") (name "Net-(*35-S2)") (class "Default")
      (node (ref "*35") (pin "2") (pinfunction "S2_2") (pintype "passive"))
      (node (ref "D35") (pin "C") (pinfunction "C_C") (pintype "passive"))
    )
    (net (code "55") (name "Net-(*36-S2)") (class "Default")
      (node (ref "*36") (pin "2") (pinfunction "S2_2") (pintype "passive"))
      (node (ref "D36") (pin "C") (pinfunction "C_C") (pintype "passive"))
    )
    (net (code "56") (name "Net-(*37-S2)") (class "Default")
      (node (ref "*37") (pin "2") (pinfunction "S2_2") (pintype "passive"))
      (node (ref "D37") (pin "C") (pinfunction "C_C") (pintype "passive"))
    )
    (net (code "57") (name "Net-(*38-S2)") (class "Default")
      (node (ref "*38") (pin "2") (pinfunction "S2_2") (pintype "passive"))
      (node (ref "D38") (pin "C") (pinfunction "C_C") (pintype "passive"))
    )
    (net (code "58") (name "Net-(*39-S2)") (class "Default")
      (node (ref "*39") (pin "2") (pinfunction "S2_2") (pintype "passive"))
      (node (ref "D39") (pin "C") (pinfunction "C_C") (pintype "passive"))
    )
    (net (code "59") (name "Net-(*40-S2)") (class "Default")
      (node (ref "*40") (pin "2") (pinfunction "S2_2") (pintype "passive"))
      (node (ref "D40") (pin "C") (pinfunction "C_C") (pintype "passive"))
    )
    (net (code "60") (name "Net-(*41-S2)") (class "Default")
      (node (ref "*41") (pin "2") (pinfunction "S2_2") (pintype "passive"))
      (node (ref "D41") (pin "C") (pinfunction "C_C") (pintype "passive"))
    )
    (net (code "61") (name "Net-(*42-S2)") (class "Default")
      (node (ref "*42") (pin "2") (pinfunction "S2_2") (pintype "passive"))
      (node (ref "D42") (pin "C") (pinfunction "C_C") (pintype "passive"))
    )
    (net (code "62") (name "Net-(*43-S2)") (class "Default")
      (node (ref "*43") (pin "2") (pinfunction "S2_2") (pintype "passive"))
      (node (ref "D43") (pin "C") (pinfunction "C_C") (pintype "passive"))
    )
    (net (code "63") (name "Net-(*44-S2)") (class "Default")
      (node (ref "*44") (pin "2") (pinfunction "S2_2") (pintype "passive"))
      (node (ref "D44") (pin "C") (pinfunction "C_C") (pintype "passive"))
    )
    (net (code "64") (name "Net-(*45-S2)") (class "Default")
      (node (ref "*45") (pin "2") (pinfunction "S2_2") (pintype "passive"))
      (node (ref "D45") (pin "C") (pinfunction "C_C") (pintype "passive"))
    )
    (net (code "65") (name "Net-(*46-S2)") (class "Default")
      (node (ref "*46") (pin "2") (pinfunction "S2_2") (pintype "passive"))
      (node (ref "D46") (pin "C") (pinfunction "C_C") (pintype "passive"))
    )
    (net (code "66") (name "Net-(*47-S2)") (class "Default")
      (node (ref "*47") (pin "2") (pinfunction "S2_2") (pintype "passive"))
      (node (ref "D47") (pin "C") (pinfunction "C_C") (pintype "passive"))
    )
    (net (code "67") (name "Net-(*48-S2)") (class "Default")
      (node (ref "*48") (pin "2") (pinfunction "S2_2") (pintype "passive"))
      (node (ref "D48") (pin "C") (pinfunction "C_C") (pintype "passive"))
    )
    (net (code "68") (name "Net-(*49-S2)") (class "Default")
      (node (ref "*49") (pin "2") (pinfunction "S2_2") (pintype "passive"))
      (node (ref "D49") (pin "C") (pinfunction "C_C") (pintype "passive"))
    )
    (net (code "69") (name "Net-(*50-S2)") (class "Default")
      (node (ref "*50") (pin "2") (pinfunction "S2_2") (pintype "passive"))
      (node (ref "D50") (pin "C") (pinfunction "C_C") (pintype "passive"))
    )
    (net (code "70") (name "Net-(*51-S2)") (class "Default")
      (node (ref "*51") (pin "2") (pinfunction "S2_2") (pintype "passive"))
      (node (ref "D51") (pin "C") (pinfunction "C_C") (pintype "passive"))
    )
    (net (code "71") (name "Net-(*52-S2)") (class "Default")
      (node (ref "*52") (pin "2") (pinfunction "S2_2") (pintype "passive"))
      (node (ref "D52") (pin "C") (pinfunction "C_C") (pintype "passive"))
    )
    (net (code "72") (name "Net-(*53-S2)") (class "Default")
      (node (ref "*53") (pin "2") (pinfunction "S2_2") (pintype "passive"))
      (node (ref "D53") (pin "C") (pinfunction "C_C") (pintype "passive"))
    )
    (net (code "73") (name "Net-(*54-S2)") (class "Default")
      (node (ref "*54") (pin "2") (pinfunction "S2_2") (pintype "passive"))
      (node (ref "D54") (pin "C") (pinfunction "C_C") (pintype "passive"))
    )
    (net (code "74") (name "Net-(*55-S2)") (class "Default")
      (node (ref "*55") (pin "2") (pinfunction "S2_2") (pintype "passive"))
      (node (ref "D55") (pin "C") (pinfunction "C_C") (pintype "passive"))
    )
    (net (code "75") (name "Net-(*56-S2)") (class "Default")
      (node (ref "*56") (pin "2") (pinfunction "S2_2") (pintype "passive"))
      (node (ref "D56") (pin "C") (pinfunction "C_C") (pintype "passive"))
    )
    (net (code "76") (name "Net-(*57-S2)") (class "Default")
      (node (ref "*57") (pin "2") (pinfunction "S2_2") (pintype "passive"))
      (node (ref "D57") (pin "C") (pinfunction "C_C") (pintype "passive"))
    )
    (net (code "77") (name "Net-(*58-S2)") (class "Default")
      (node (ref "*58") (pin "2") (pinfunction "S2_2") (pintype "passive"))
      (node (ref "D58") (pin "C") (pinfunction "C_C") (pintype "passive"))
    )
    (net (code "78") (name "Net-(*59-S2)") (class "Default")
      (node (ref "*59") (pin "2") (pinfunction "S2_2") (pintype "passive"))
      (node (ref "D59") (pin "C") (pinfunction "C_C") (pintype "passive"))
    )
    (net (code "79") (name "Net-(*60-S2)") (class "Default")
      (node (ref "*60") (pin "2") (pinfunction "S2_2") (pintype "passive"))
      (node (ref "D60") (pin "C") (pinfunction "C_C") (pintype "passive"))
    )
    (net (code "80") (name "Net-(*61-S2)") (class "Default")
      (node (ref "*61") (pin "2") (pinfunction "S2_2") (pintype "passive"))
      (node (ref "D61") (pin "C") (pinfunction "C_C") (pintype "passive"))
    )
    (net (code "81") (name "Net-(*62-S2)") (class "Default")
      (node (ref "*62") (pin "2") (pinfunction "S2_2") (pintype "passive"))
      (node (ref "D62") (pin "C") (pinfunction "C_C") (pintype "passive"))
    )
    (net (code "82") (name "unconnected-(*1-S3-Pad3)") (class "Default")
      (node (ref "*1") (pin "3") (pinfunction "S3_3") (pintype "passive"))
    )
    (net (code "83") (name "unconnected-(*1-S4-Pad4)") (class "Default")
      (node (ref "*1") (pin "4") (pinfunction "S4_4") (pintype "passive"))
    )
    (net (code "84") (name "unconnected-(*2-S3-Pad3)") (class "Default")
      (node (ref "*2") (pin "3") (pinfunction "S3_3") (pintype "passive"))
    )
    (net (code "85") (name "unconnected-(*2-S4-Pad4)") (class "Default")
      (node (ref "*2") (pin "4") (pinfunction "S4_4") (pintype "passive"))
    )
    (net (code "86") (name "unconnected-(*3-S3-Pad3)") (class "Default")
      (node (ref "*3") (pin "3") (pinfunction "S3_3") (pintype "passive"))
    )
    (net (code "87") (name "unconnected-(*3-S4-Pad4)") (class "Default")
      (node (ref "*3") (pin "4") (pinfunction "S4_4") (pintype "passive"))
    )
    (net (code "88") (name "unconnected-(*4-S3-Pad3)") (class "Default")
      (node (ref "*4") (pin "3") (pinfunction "S3_3") (pintype "passive"))
    )
    (net (code "89") (name "unconnected-(*4-S4-Pad4)") (class "Default")
      (node (ref "*4") (pin "4") (pinfunction "S4_4") (pintype "passive"))
    )
    (net (code "90") (name "unconnected-(*5-S3-Pad3)") (class "Default")
      (node (ref "*5") (pin "3") (pinfunction "S3_3") (pintype "passive"))
    )
    (net (code "91") (name "unconnected-(*5-S4-Pad4)") (class "Default")
      (node (ref "*5") (pin "4") (pinfunction "S4_4") (pintype "passive"))
    )
    (net (code "92") (name "unconnected-(*6-S3-Pad3)") (class "Default")
      (node (ref "*6") (pin "3") (pinfunction "S3_3") (pintype "passive"))
    )
    (net (code "93") (name "unconnected-(*6-S4-Pad4)") (class "Default")
      (node (ref "*6") (pin "4") (pinfunction "S4_4") (pintype "passive"))
    )
    (net (code "94") (name "unconnected-(*7-S3-Pad3)") (class "Default")
      (node (ref "*7") (pin "3") (pinfunction "S3_3") (pintype "passive"))
    )
    (net (code "95") (name "unconnected-(*7-S4-Pad4)") (class "Default")
      (node (ref "*7") (pin "4") (pinfunction "S4_4") (pintype "passive"))
    )
    (net (code "96") (name "unconnected-(*8-S3-Pad3)") (class "Default")
      (node (ref "*8") (pin "3") (pinfunction "S3_3") (pintype "passive"))
    )
    (net (code "97") (name "unconnected-(*8-S4-Pad4)") (class "Default")
      (node (ref "*8") (pin "4") (pinfunction "S4_4") (pintype "passive"))
    )
    (net (code "98") (name "unconnected-(*9-S3-Pad3)") (class "Default")
      (node (ref "*9") (pin "3") (pinfunction "S3_3") (pintype "passive"))
    )
    (net (code "99") (name "unconnected-(*9-S4-Pad4)") (class "Default")
      (node (ref "*9") (pin "4") (pinfunction "S4_4") (pintype "passive"))
    )
    (net (code "100") (name "unconnected-(*10-S3-Pad3)") (class "Default")
      (node (ref "*10") (pin "3") (pinfunction "S3_3") (pintype "passive"))
    )
    (net (code "101") (name "unconnected-(*10-S4-Pad4)") (class "Default")
      (node (ref "*10") (pin "4") (pinfunction "S4_4") (pintype "passive"))
    )
    (net (code "102") (name "unconnected-(*11-S3-Pad3)") (class "Default")
      (node (ref "*11") (pin "3") (pinfunction "S3_3") (pintype "passive"))
    )
    (net (code "103") (name "unconnected-(*11-S4-Pad4)") (class "Default")
      (node (ref "*11") (pin "4") (pinfunction "S4_4") (pintype "passive"))
    )
    (net (code "104") (name "unconnected-(*12-S3-Pad3)") (class "Default")
      (node (ref "*12") (pin "3") (pinfunction "S3_3") (pintype "passive"))
    )
    (net (code "105") (name "unconnected-(*12-S4-Pad4)") (class "Default")
      (node (ref "*12") (pin "4") (pinfunction "S4_4") (pintype "passive"))
    )
    (net (code "106") (name "unconnected-(*13-S3-Pad3)") (class "Default")
      (node (ref "*13") (pin "3") (pinfunction "S3_3") (pintype "passive"))
    )
    (net (code "107") (name "unconnected-(*13-S4-Pad4)") (class "Default")
      (node (ref "*13") (pin "4") (pinfunction "S4_4") (pintype "passive"))
    )
    (net (code "108") (name "unconnected-(*14-S3-Pad3)") (class "Default")
      (node (ref "*14") (pin "3") (pinfunction "S3_3") (pintype "passive"))
    )
    (net (code "109") (name "unconnected-(*14-S4-Pad4)") (class "Default")
      (node (ref "*14") (pin "4") (pinfunction "S4_4") (pintype "passive"))
    )
    (net (code "110") (name "unconnected-(*15-S3-Pad3)") (class "Default")
      (node (ref "*15") (pin "3") (pinfunction "S3_3") (pintype "passive"))
    )
    (net (code "111") (name "unconnected-(*15-S4-Pad4)") (class "Default")
      (node (ref "*15") (pin "4") (pinfunction "S4_4") (pintype "passive"))
    )
    (net (code "112") (name "unconnected-(*16-S3-Pad3)") (class "Default")
      (node (ref "*16") (pin "3") (pinfunction "S3_3") (pintype "passive"))
    )
    (net (code "113") (name "unconnected-(*16-S4-Pad4)") (class "Default")
      (node (ref "*16") (pin "4") (pinfunction "S4_4") (pintype "passive"))
    )
    (net (code "114") (name "unconnected-(*17-S3-Pad3)") (class "Default")
      (node (ref "*17") (pin "3") (pinfunction "S3_3") (pintype "passive"))
    )
    (net (code "115") (name "unconnected-(*17-S4-Pad4)") (class "Default")
      (node (ref "*17") (pin "4") (pinfunction "S4_4") (pintype "passive"))
    )
    (net (code "116") (name "unconnected-(*18-S3-Pad3)") (class "Default")
      (node (ref "*18") (pin "3") (pinfunction "S3_3") (pintype "passive"))
    )
    (net (code "117") (name "unconnected-(*18-S4-Pad4)") (class "Default")
      (node (ref "*18") (pin "4") (pinfunction "S4_4") (pintype "passive"))
    )
    (net (code "118") (name "unconnected-(*19-S3-Pad3)") (class "Default")
      (node (ref "*19") (pin "3") (pinfunction "S3_3") (pintype "passive"))
    )
    (net (code "119") (name "unconnected-(*19-S4-Pad4)") (class "Default")
      (node (ref "*19") (pin "4") (pinfunction "S4_4") (pintype "passive"))
    )
    (net (code "120") (name "unconnected-(*20-S3-Pad3)") (class "Default")
      (node (ref "*20") (pin "3") (pinfunction "S3_3") (pintype "passive"))
    )
    (net (code "121") (name "unconnected-(*20-S4-Pad4)") (class "Default")
      (node (ref "*20") (pin "4") (pinfunction "S4_4") (pintype "passive"))
    )
    (net (code "122") (name "unconnected-(*21-S3-Pad3)") (class "Default")
      (node (ref "*21") (pin "3") (pinfunction "S3_3") (pintype "passive"))
    )
    (net (code "123") (name "unconnected-(*21-S4-Pad4)") (class "Default")
      (node (ref "*21") (pin "4") (pinfunction "S4_4") (pintype "passive"))
    )
    (net (code "124") (name "unconnected-(*22-S3-Pad3)") (class "Default")
      (node (ref "*22") (pin "3") (pinfunction "S3_3") (pintype "passive"))
    )
    (net (code "125") (name "unconnected-(*22-S4-Pad4)") (class "Default")
      (node (ref "*22") (pin "4") (pinfunction "S4_4") (pintype "passive"))
    )
    (net (code "126") (name "unconnected-(*23-S3-Pad3)") (class "Default")
      (node (ref "*23") (pin "3") (pinfunction "S3_3") (pintype "passive"))
    )
    (net (code "127") (name "unconnected-(*23-S4-Pad4)") (class "Default")
      (node (ref "*23") (pin "4") (pinfunction "S4_4") (pintype "passive"))
    )
    (net (code "128") (name "unconnected-(*24-S3-Pad3)") (class "Default")
      (node (ref "*24") (pin "3") (pinfunction "S3_3") (pintype "passive"))
    )
    (net (code "129") (name "unconnected-(*24-S4-Pad4)") (class "Default")
      (node (ref "*24") (pin "4") (pinfunction "S4_4") (pintype "passive"))
    )
    (net (code "130") (name "unconnected-(*25-S3-Pad3)") (class "Default")
      (node (ref "*25") (pin "3") (pinfunction "S3_3") (pintype "passive"))
    )
    (net (code "131") (name "unconnected-(*25-S4-Pad4)") (class "Default")
      (node (ref "*25") (pin "4") (pinfunction "S4_4") (pintype "passive"))
    )
    (net (code "132") (name "unconnected-(*26-S3-Pad3)") (class "Default")
      (node (ref "*26") (pin "3") (pinfunction "S3_3") (pintype "passive"))
    )
    (net (code "133") (name "unconnected-(*26-S4-Pad4)") (class "Default")
      (node (ref "*26") (pin "4") (pinfunction "S4_4") (pintype "passive"))
    )
    (net (code "134") (name "unconnected-(*27-S3-Pad3)") (class "Default")
      (node (ref "*27") (pin "3") (pinfunction "S3_3") (pintype "passive"))
    )
    (net (code "135") (name "unconnected-(*27-S4-Pad4)") (class "Default")
      (node (ref "*27") (pin "4") (pinfunction "S4_4") (pintype "passive"))
    )
    (net (code "136") (name "unconnected-(*28-S3-Pad3)") (class "Default")
      (node (ref "*28") (pin "3") (pinfunction "S3_3") (pintype "passive"))
    )
    (net (code "137") (name "unconnected-(*28-S4-Pad4)") (class "Default")
      (node (ref "*28") (pin "4") (pinfunction "S4_4") (pintype "passive"))
    )
    (net (code "138") (name "unconnected-(*29-S3-Pad3)") (class "Default")
      (node (ref "*29") (pin "3") (pinfunction "S3_3") (pintype "passive"))
    )
    (net (code "139") (name "unconnected-(*29-S4-Pad4)") (class "Default")
      (node (ref "*29") (pin "4") (pinfunction "S4_4") (pintype "passive"))
    )
    (net (code "140") (name "unconnected-(*30-S3-Pad3)") (class "Default")
      (node (ref "*30") (pin "3") (pinfunction "S3_3") (pintype "passive"))
    )
    (net (code "141") (name "unconnected-(*30-S4-Pad4)") (class "Default")
      (node (ref "*30") (pin "4") (pinfunction "S4_4") (pintype "passive"))
    )
    (net (code "142") (name "unconnected-(*31-S3-Pad3)") (class "Default")
      (node (ref "*31") (pin "3") (pinfunction "S3_3") (pintype "passive"))
    )
    (net (code "143") (name "unconnected-(*31-S4-Pad4)") (class "Default")
      (node (ref "*31") (pin "4") (pinfunction "S4_4") (pintype "passive"))
    )
    (net (code "144") (name "unconnected-(*32-S3-Pad3)") (class "Default")
      (node (ref "*32") (pin "3") (pinfunction "S3_3") (pintype "passive"))
    )
    (net (code "145") (name "unconnected-(*32-S4-Pad4)") (class "Default")
      (node (ref "*32") (pin "4") (pinfunction "S4_4") (pintype "passive"))
    )
    (net (code "146") (name "unconnected-(*33-S3-Pad3)") (class "Default")
      (node (ref "*33") (pin "3") (pinfunction "S3_3") (pintype "passive"))
    )
    (net (code "147") (name "unconnected-(*33-S4-Pad4)") (class "Default")
      (node (ref "*33") (pin "4") (pinfunction "S4_4") (pintype "passive"))
    )
    (net (code "148") (name "unconnected-(*34-S3-Pad3)") (class "Default")
      (node (ref "*34") (pin "3") (pinfunction "S3_3") (pintype "passive"))
    )
    (net (code "149") (name "unconnected-(*34-S4-Pad4)") (class "Default")
      (node (ref "*34") (pin "4") (pinfunction "S4_4") (pintype "passive"))
    )
    (net (code "150") (name "unconnected-(*35-S3-Pad3)") (class "Default")
      (node (ref "*35") (pin "3") (pinfunction "S3_3") (pintype "passive"))
    )
    (net (code "151") (name "unconnected-(*35-S4-Pad4)") (class "Default")
      (node (ref "*35") (pin "4") (pinfunction "S4_4") (pintype "passive"))
    )
    (net (code "152") (name "unconnected-(*36-S3-Pad3)") (class "Default")
      (node (ref "*36") (pin "3") (pinfunction "S3_3") (pintype "passive"))
    )
    (net (code "153") (name "unconnected-(*36-S4-Pad4)") (class "Default")
      (node (ref "*36") (pin "4") (pinfunction "S4_4") (pintype "passive"))
    )
    (net (code "154") (name "unconnected-(*37-S3-Pad3)") (class "Default")
      (node (ref "*37") (pin "3") (pinfunction "S3_3") (pintype "passive"))
    )
    (net (code "155") (name "unconnected-(*37-S4-Pad4)") (class "Default")
      (node (ref "*37") (pin "4") (pinfunction "S4_4") (pintype "passive"))
    )
    (net (code "156") (name "unconnected-(*38-S3-Pad3)") (class "Default")
      (node (ref "*38") (pin "3") (pinfunction "S3_3") (pintype "passive"))
    )
    (net (code "157") (name "unconnected-(*38-S4-Pad4)") (class "Default")
      (node (ref "*38") (pin "4") (pinfunction "S4_4") (pintype "passive"))
    )
    (net (code "158") (name "unconnected-(*39-S3-Pad3)") (class "Default")
      (node (ref "*39") (pin "3") (pinfunction "S3_3") (pintype "passive"))
    )
    (net (code "159") (name "unconnected-(*39-S4-Pad4)") (class "Default")
      (node (ref "*39") (pin "4") (pinfunction "S4_4") (pintype "passive"))
    )
    (net (code "160") (name "unconnected-(*40-S3-Pad3)") (class "Default")
      (node (ref "*40") (pin "3") (pinfunction "S3_3") (pintype "passive"))
    )
    (net (code "161") (name "unconnected-(*40-S4-Pad4)") (class "Default")
      (node (ref "*40") (pin "4") (pinfunction "S4_4") (pintype "passive"))
    )
    (net (code "162") (name "unconnected-(*41-S3-Pad3)") (class "Default")
      (node (ref "*41") (pin "3") (pinfunction "S3_3") (pintype "passive"))
    )
    (net (code "163") (name "unconnected-(*41-S4-Pad4)") (class "Default")
      (node (ref "*41") (pin "4") (pinfunction "S4_4") (pintype "passive"))
    )
    (net (code "164") (name "unconnected-(*42-S3-Pad3)") (class "Default")
      (node (ref "*42") (pin "3") (pinfunction "S3_3") (pintype "passive"))
    )
    (net (code "165") (name "unconnected-(*42-S4-Pad4)") (class "Default")
      (node (ref "*42") (pin "4") (pinfunction "S4_4") (pintype "passive"))
    )
    (net (code "166") (name "unconnected-(*43-S3-Pad3)") (class "Default")
      (node (ref "*43") (pin "3") (pinfunction "S3_3") (pintype "passive"))
    )
    (net (code "167") (name "unconnected-(*43-S4-Pad4)") (class "Default")
      (node (ref "*43") (pin "4") (pinfunction "S4_4") (pintype "passive"))
    )
    (net (code "168") (name "unconnected-(*44-S3-Pad3)") (class "Default")
      (node (ref "*44") (pin "3") (pinfunction "S3_3") (pintype "passive"))
    )
    (net (code "169") (name "unconnected-(*44-S4-Pad4)") (class "Default")
      (node (ref "*44") (pin "4") (pinfunction "S4_4") (pintype "passive"))
    )
    (net (code "170") (name "unconnected-(*45-S3-Pad3)") (class "Default")
      (node (ref "*45") (pin "3") (pinfunction "S3_3") (pintype "passive"))
    )
    (net (code "171") (name "unconnected-(*45-S4-Pad4)") (class "Default")
      (node (ref "*45") (pin "4") (pinfunction "S4_4") (pintype "passive"))
    )
    (net (code "172") (name "unconnected-(*46-S3-Pad3)") (class "Default")
      (node (ref "*46") (pin "3") (pinfunction "S3_3") (pintype "passive"))
    )
    (net (code "173") (name "unconnected-(*46-S4-Pad4)") (class "Default")
      (node (ref "*46") (pin "4") (pinfunction "S4_4") (pintype "passive"))
    )
    (net (code "174") (name "unconnected-(*47-S3-Pad3)") (class "Default")
      (node (ref "*47") (pin "3") (pinfunction "S3_3") (pintype "passive"))
    )
    (net (code "175") (name "unconnected-(*47-S4-Pad4)") (class "Default")
      (node (ref "*47") (pin "4") (pinfunction "S4_4") (pintype "passive"))
    )
    (net (code "176") (name "unconnected-(*48-S3-Pad3)") (class "Default")
      (node (ref "*48") (pin "3") (pinfunction "S3_3") (pintype "passive"))
    )
    (net (code "177") (name "unconnected-(*48-S4-Pad4)") (class "Default")
      (node (ref "*48") (pin "4") (pinfunction "S4_4") (pintype "passive"))
    )
    (net (code "178") (name "unconnected-(*49-S3-Pad3)") (class "Default")
      (node (ref "*49") (pin "3") (pinfunction "S3_3") (pintype "passive"))
    )
    (net (code "179") (name "unconnected-(*49-S4-Pad4)") (class "Default")
      (node (ref "*49") (pin "4") (pinfunction "S4_4") (pintype "passive"))
    )
    (net (code "180") (name "unconnected-(*50-S3-Pad3)") (class "Default")
      (node (ref "*50") (pin "3") (pinfunction "S3_3") (pintype "passive"))
    )
    (net (code "181") (name "unconnected-(*50-S4-Pad4)") (class "Default")
      (node (ref "*50") (pin "4") (pinfunction "S4_4") (pintype "passive"))
    )
    (net (code "182") (name "unconnected-(*51-S3-Pad3)") (class "Default")
      (node (ref "*51") (pin "3") (pinfunction "S3_3") (pintype "passive"))
    )
    (net (code "183") (name "unconnected-(*51-S4-Pad4)") (class "Default")
      (node (ref "*51") (pin "4") (pinfunction "S4_4") (pintype "passive"))
    )
    (net (code "184") (name "unconnected-(*52-S3-Pad3)") (class "Default")
      (node (ref "*52") (pin "3") (pinfunction "S3_3") (pintype "passive"))
    )
    (net (code "185") (name "unconnected-(*52-S4-Pad4)") (class "Default")
      (node (ref "*52") (pin "4") (pinfunction "S4_4") (pintype "passive"))
    )
    (net (code "186") (name "unconnected-(*53-S3-Pad3)") (class "Default")
      (node (ref "*53") (pin "3") (pinfunction "S3_3") (pintype "passive"))
    )
    (net (code "187") (name "unconnected-(*53-S4-Pad4)") (class "Default")
      (node (ref "*53") (pin "4") (pinfunction "S4_4") (pintype "passive"))
    )
    (net (code "188") (name "unconnected-(*54-S3-Pad3)") (class "Default")
      (node (ref "*54") (pin "3") (pinfunction "S3_3") (pintype "passive"))
    )
    (net (code "189") (name "unconnected-(*54-S4-Pad4)") (class "Default")
      (node (ref "*54") (pin "4") (pinfunction "S4_4") (pintype "passive"))
    )
    (net (code "190") (name "unconnected-(*55-S3-Pad3)") (class "Default")
      (node (ref "*55") (pin "3") (pinfunction "S3_3") (pintype "passive"))
    )
    (net (code "191") (name "unconnected-(*55-S4-Pad4)") (class "Default")
      (node (ref "*55") (pin "4") (pinfunction "S4_4") (pintype "passive"))
    )
    (net (code "192") (name "unconnected-(*56-S3-Pad3)") (class "Default")
      (node (ref "*56") (pin "3") (pinfunction "S3_3") (pintype "passive"))
    )
    (net (code "193") (name "unconnected-(*56-S4-Pad4)") (class "Default")
      (node (ref "*56") (pin "4") (pinfunction "S4_4") (pintype "passive"))
    )
    (net (code "194") (name "unconnected-(*57-S3-Pad3)") (class "Default")
      (node (ref "*57") (pin "3") (pinfunction "S3_3") (pintype "passive"))
    )
    (net (code "195") (name "unconnected-(*57-S4-Pad4)") (class "Default")
      (node (ref "*57") (pin "4") (pinfunction "S4_4") (pintype "passive"))
    )
    (net (code "196") (name "unconnected-(*58-S3-Pad3)") (class "Default")
      (node (ref "*58") (pin "3") (pinfunction "S3_3") (pintype "passive"))
    )
    (net (code "197") (name "unconnected-(*58-S4-Pad4)") (class "Default")
      (node (ref "*58") (pin "4") (pinfunction "S4_4") (pintype "passive"))
    )
    (net (code "198") (name "unconnected-(*59-S3-Pad3)") (class "Default")
      (node (ref "*59") (pin "3") (pinfunction "S3_3") (pintype "passive"))
    )
    (net (code "199") (name "unconnected-(*59-S4-Pad4)") (class "Default")
      (node (ref "*59") (pin "4") (pinfunction "S4_4") (pintype "passive"))
    )
    (net (code "200") (name "unconnected-(*60-S3-Pad3)") (class "Default")
      (node (ref "*60") (pin "3") (pinfunction "S3_3") (pintype "passive"))
    )
    (net (code "201") (name "unconnected-(*60-S4-Pad4)") (class "Default")
      (node (ref "*60") (pin "4") (pinfunction "S4_4") (pintype "passive"))
    )
    (net (code "202") (name "unconnected-(*61-S3-Pad3)") (class "Default")
      (node (ref "*61") (pin "3") (pinfunction "S3_3") (pintype "passive"))
    )
    (net (code "203") (name "unconnected-(*61-S4-Pad4)") (class "Default")
      (node (ref "*61") (pin "4") (pinfunction "S4_4") (pintype "passive"))
    )
    (net (code "204") (name "unconnected-(*62-S3-Pad3)") (class "Default")
      (node (ref "*62") (pin "3") (pinfunction "S3_3") (pintype "passive"))
    )
    (net (code "205") (name "unconnected-(*62-S4-Pad4)") (class "Default")
      (node (ref "*62") (pin "4") (pinfunction "S4_4") (pintype "passive"))
    )
  )
)
